# CANBed_FD.net
KiCad netlist of a schematic drawn in EAGLE
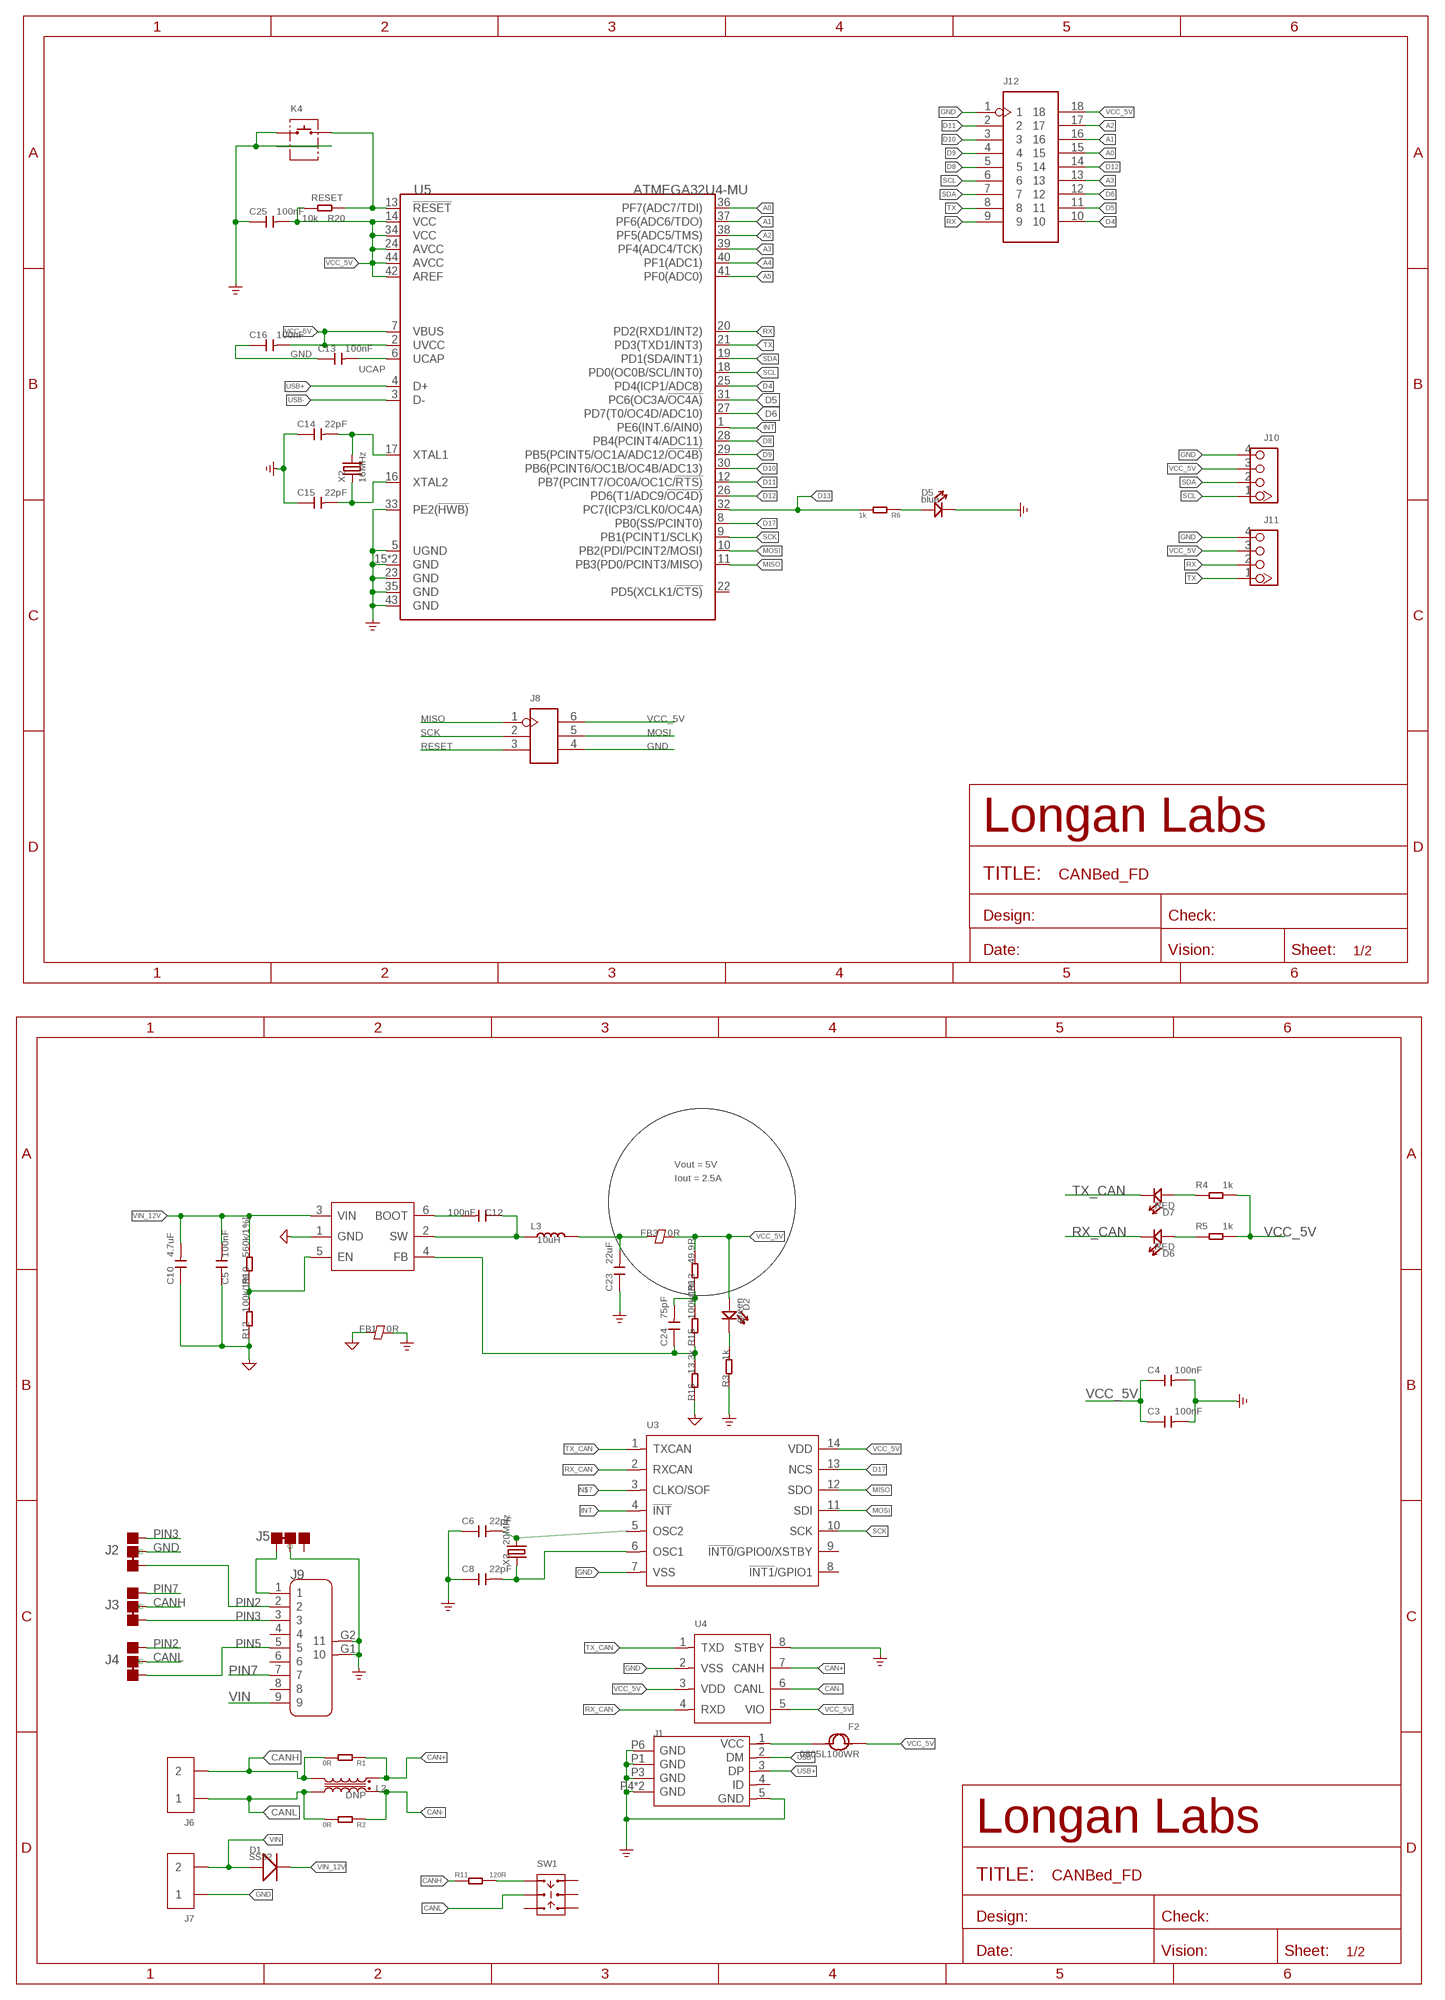
[diagram p0: schematic, sheet 1]

(export (version "E")
  (design (tool "Eeschema 10.0.6"))
  (components
    (comp (ref "C3")
      (value "100nF")
      (footprint "eagle-import:C0603")
      (libsource (lib "eagle-import") (part "CAP-0603"))
    )
    (comp (ref "C4")
      (value "100nF")
      (footprint "eagle-import:C0603")
      (libsource (lib "eagle-import") (part "CAP-0603"))
    )
    (comp (ref "C5")
      (value "100nF")
      (footprint "eagle-import:C0603")
      (libsource (lib "eagle-import") (part "CAP-0603"))
    )
    (comp (ref "C6")
      (value "22pF")
      (footprint "eagle-import:C0603")
      (libsource (lib "eagle-import") (part "CAP-0603"))
    )
    (comp (ref "C8")
      (value "22pF")
      (footprint "eagle-import:C0603")
      (libsource (lib "eagle-import") (part "CAP-0603"))
    )
    (comp (ref "C10")
      (value "4.7uF")
      (footprint "eagle-import:C1206")
      (libsource (lib "eagle-import") (part "CAP-1206"))
    )
    (comp (ref "C12")
      (value "100nF")
      (footprint "eagle-import:C0603")
      (libsource (lib "eagle-import") (part "CAP-0603"))
    )
    (comp (ref "C13")
      (value "100nF")
      (footprint "eagle-import:C0603")
      (libsource (lib "eagle-import") (part "CAP-0603"))
    )
    (comp (ref "C14")
      (value "22pF")
      (footprint "eagle-import:C0603")
      (libsource (lib "eagle-import") (part "CAP-0603"))
    )
    (comp (ref "C15")
      (value "22pF")
      (footprint "eagle-import:C0603")
      (libsource (lib "eagle-import") (part "CAP-0603"))
    )
    (comp (ref "C16")
      (value "100nF")
      (footprint "eagle-import:C0603")
      (libsource (lib "eagle-import") (part "CAP-0603"))
    )
    (comp (ref "C23")
      (value "22uF")
      (footprint "eagle-import:C1206")
      (libsource (lib "eagle-import") (part "CAP-1206"))
    )
    (comp (ref "C24")
      (value "75pF")
      (footprint "eagle-import:C0603")
      (libsource (lib "eagle-import") (part "CAP-0603"))
    )
    (comp (ref "C25")
      (value "100nF")
      (footprint "eagle-import:C0603")
      (libsource (lib "eagle-import") (part "CAP-0603"))
    )
    (comp (ref "D1")
      (value "SS32")
      (footprint "eagle-import:DO-214AC")
      (libsource (lib "eagle-import") (part "DIODE'SMA'"))
    )
    (comp (ref "D2")
      (value "green")
      (footprint "eagle-import:LED-0603")
      (libsource (lib "eagle-import") (part "LED'0603'"))
    )
    (comp (ref "D5")
      (value "blue")
      (footprint "eagle-import:LED-0603")
      (libsource (lib "eagle-import") (part "LED'0603'"))
    )
    (comp (ref "D6")
      (value "RED")
      (footprint "eagle-import:LED-0603")
      (libsource (lib "eagle-import") (part "LED'0603'"))
    )
    (comp (ref "D7")
      (value "RED")
      (footprint "eagle-import:LED-0603")
      (libsource (lib "eagle-import") (part "LED'0603'"))
    )
    (comp (ref "F2")
      (value "0805L100WR")
      (footprint "eagle-import:F0805")
      (libsource (lib "eagle-import") (part "FUSE0805"))
    )
    (comp (ref "FB1")
      (value "0R")
      (footprint "eagle-import:F0805")
      (libsource (lib "eagle-import") (part "FERRITE-BEAD-0805"))
    )
    (comp (ref "FB3")
      (value "0R")
      (footprint "eagle-import:F0805")
      (libsource (lib "eagle-import") (part "FERRITE-BEAD-0805"))
    )
    (comp (ref "J1")
      (value "MICRO-USB5+4P-320010050")
      (footprint "eagle-import:MICRO-USB5+5P-SMD-0.65-7.2X5.06MM")
      (libsource (lib "eagle-import") (part "MICRO-USB5+4P-320010050"))
    )
    (comp (ref "J2")
      (value "JUMPER-3P-SHORT")
      (footprint "eagle-import:3P-SMD-SHORT")
      (libsource (lib "eagle-import") (part "JUMPER-3P-SHORT"))
    )
    (comp (ref "J3")
      (value "JUMPER-3P-SHORT")
      (footprint "eagle-import:3P-SMD-SHORT")
      (libsource (lib "eagle-import") (part "JUMPER-3P-SHORT"))
    )
    (comp (ref "J4")
      (value "JUMPER-3P-SHORT")
      (footprint "eagle-import:3P-SMD-SHORT")
      (libsource (lib "eagle-import") (part "JUMPER-3P-SHORT"))
    )
    (comp (ref "J5")
      (value "JUMPER-3P-SHORT")
      (footprint "eagle-import:3P-SMD-SHORT")
      (libsource (lib "eagle-import") (part "JUMPER-3P-SHORT"))
    )
    (comp (ref "J6")
      (value "SCREW-TERMINAL-2P'5.08'")
      (footprint "eagle-import:H2-5.0-10.5X8.0MM")
      (libsource (lib "eagle-import") (part "SCREW-TERMINAL-2P'5.08'"))
    )
    (comp (ref "J7")
      (value "SCREW-TERMINAL-2P'5.08'")
      (footprint "eagle-import:H2-5.0-10.5X8.0MM")
      (libsource (lib "eagle-import") (part "SCREW-TERMINAL-2P'5.08'"))
    )
    (comp (ref "J8")
      (value "HEADER-2X3P-2.54")
      (footprint "eagle-import:H2X3-2.54")
      (libsource (lib "eagle-import") (part "HEADER-2X3P-2.54"))
    )
    (comp (ref "J9")
      (value "DB9'MEAL'")
      (footprint "eagle-import:DB9-MEAL")
      (libsource (lib "eagle-import") (part "DB9'MEAL'"))
    )
    (comp (ref "J10")
      (value "320110033")
      (footprint "eagle-import:HW4-2.0")
      (libsource (lib "eagle-import") (part "GROVE-CONNECTOR-DIP-2.0"))
    )
    (comp (ref "J11")
      (value "320110033")
      (footprint "eagle-import:HW4-2.0")
      (libsource (lib "eagle-import") (part "GROVE-CONNECTOR-DIP-2.0"))
    )
    (comp (ref "J12")
      (value "HEADER-2X9P-2.54")
      (footprint "eagle-import:H2X9-2.54")
      (libsource (lib "eagle-import") (part "HEADER-2X9P-2.54"))
    )
    (comp (ref "K4")
      (value "BUTTON-2+2P")
      (footprint "eagle-import:SW2+2P-7.7X2.75X3.95MM")
      (libsource (lib "eagle-import") (part "BUTTON-2+2P"))
    )
    (comp (ref "L2")
      (value "DNP")
      (footprint "eagle-import:INT4-0.85-2X1.25X1.2MM")
      (libsource (lib "eagle-import") (part "INDUCTOR-COMMON-MODE-SRF2012-900YA"))
    )
    (comp (ref "L3")
      (value "10uH")
      (footprint "eagle-import:INT2-SMD-6.6X7.1X3MM")
      (libsource (lib "eagle-import") (part "INDUCTOR-6.6X7.1"))
    )
    (comp (ref "R1")
      (value "0R")
      (footprint "eagle-import:R0603")
      (libsource (lib "eagle-import") (part "RES-0603"))
    )
    (comp (ref "R2")
      (value "0R")
      (footprint "eagle-import:R0603")
      (libsource (lib "eagle-import") (part "RES-0603"))
    )
    (comp (ref "R3")
      (value "1k")
      (footprint "eagle-import:R0603")
      (libsource (lib "eagle-import") (part "RES-0603"))
    )
    (comp (ref "R4")
      (value "1k")
      (footprint "eagle-import:R0603")
      (libsource (lib "eagle-import") (part "RES-0603"))
    )
    (comp (ref "R5")
      (value "1k")
      (footprint "eagle-import:R0603")
      (libsource (lib "eagle-import") (part "RES-0603"))
    )
    (comp (ref "R6")
      (value "1k")
      (footprint "eagle-import:R0603")
      (libsource (lib "eagle-import") (part "RES-0603"))
    )
    (comp (ref "R10")
      (value "560k/1%]")
      (footprint "eagle-import:R0603")
      (libsource (lib "eagle-import") (part "RES-0603"))
    )
    (comp (ref "R11")
      (value "120R")
      (footprint "eagle-import:R0603")
      (libsource (lib "eagle-import") (part "RES-0603"))
    )
    (comp (ref "R12")
      (value "100k/1%")
      (footprint "eagle-import:R0603")
      (libsource (lib "eagle-import") (part "RES-0603"))
    )
    (comp (ref "R13")
      (value "49.9R")
      (footprint "eagle-import:R0603")
      (libsource (lib "eagle-import") (part "RES-0603"))
    )
    (comp (ref "R15")
      (value "100k/1%")
      (footprint "eagle-import:R0603")
      (libsource (lib "eagle-import") (part "RES-0603"))
    )
    (comp (ref "R16")
      (value "13.3k")
      (footprint "eagle-import:R0603")
      (libsource (lib "eagle-import") (part "RES-0603"))
    )
    (comp (ref "R20")
      (value "10k")
      (footprint "eagle-import:R0603")
      (libsource (lib "eagle-import") (part "RES-0603"))
    )
    (comp (ref "SW1")
      (value "SWITCH-2CH-6P-311010004")
      (footprint "eagle-import:SW6-2.54-9.0X3.5X3.2+2.0MM")
      (libsource (lib "eagle-import") (part "SWITCH-2CH-6P-311010004"))
    )
    (comp (ref "U$11")
      (value "PMIC-TPS54302")
      (footprint "eagle-import:SOT-23-6")
      (libsource (lib "eagle-import") (part "PMIC-TPS54302"))
    )
    (comp (ref "U3")
      (value "CONTROLLER-MCP2517FD")
      (footprint "eagle-import:SOIC14-1.27-8.6X3.9MM")
      (libsource (lib "eagle-import") (part "CONTROLLER-MCP2517FD"))
    )
    (comp (ref "U4")
      (value "TRANSCEIVER-MCP2542")
      (footprint "eagle-import:SOIC8-1.27-5X4MM")
      (libsource (lib "eagle-import") (part "TRANSCEIVER-MCP2542"))
    )
    (comp (ref "U5")
      (value "ATMEGA32U4-MU")
      (footprint "eagle-import:QFN44")
      (libsource (lib "eagle-import") (part "ATMEGA32U4-MU"))
    )
    (comp (ref "X2")
      (value "16MHz")
      (footprint "eagle-import:HC49US")
      (libsource (lib "eagle-import") (part "CRYSTAL-2P'HC49US'"))
    )
    (comp (ref "X3")
      (value "20MHz")
      (footprint "eagle-import:HC49US")
      (libsource (lib "eagle-import") (part "CRYSTAL-2P'HC49US'"))
    )
  )
  (nets
    (net (code "1") (name "A0") (class "Default")
      (node (ref "J12") (pin "15") (pinfunction "15_15") (pintype "bidirectional"))
      (node (ref "U5") (pin "36") (pinfunction "PF7(ADC7/TDI)_36") (pintype "bidirectional"))
    )
    (net (code "2") (name "A1") (class "Default")
      (node (ref "J12") (pin "16") (pinfunction "16_16") (pintype "bidirectional"))
      (node (ref "U5") (pin "37") (pinfunction "PF6(ADC6/TDO)_37") (pintype "bidirectional"))
    )
    (net (code "3") (name "A2") (class "Default")
      (node (ref "J12") (pin "17") (pinfunction "17_17") (pintype "bidirectional"))
      (node (ref "U5") (pin "38") (pinfunction "PF5(ADC5/TMS)_38") (pintype "bidirectional"))
    )
    (net (code "4") (name "A3") (class "Default")
      (node (ref "J12") (pin "13") (pinfunction "13_13") (pintype "bidirectional"))
      (node (ref "U5") (pin "39") (pinfunction "PF4(ADC4/TCK)_39") (pintype "bidirectional"))
    )
    (net (code "5") (name "A4") (class "Default")
      (node (ref "U5") (pin "40") (pinfunction "PF1(ADC1)_40") (pintype "bidirectional"))
    )
    (net (code "6") (name "A5") (class "Default")
      (node (ref "U5") (pin "41") (pinfunction "PF0(ADC0)_41") (pintype "bidirectional"))
    )
    (net (code "7") (name "AGND") (class "Default")
      (node (ref "C10") (pin "1") (pinfunction "1_1") (pintype "passive"))
      (node (ref "C5") (pin "1") (pinfunction "1_1") (pintype "passive"))
      (node (ref "FB1") (pin "1") (pinfunction "1_1") (pintype "bidirectional"))
      (node (ref "R12") (pin "1") (pinfunction "1_1") (pintype "passive"))
      (node (ref "R16") (pin "1") (pinfunction "1_1") (pintype "passive"))
      (node (ref "U$11") (pin "1") (pinfunction "GND_1") (pintype "bidirectional"))
    )
    (net (code "8") (name "CAN+") (class "Default")
      (node (ref "L2") (pin "4") (pinfunction "4_4") (pintype "bidirectional"))
      (node (ref "R1") (pin "1") (pinfunction "1_1") (pintype "passive"))
      (node (ref "U4") (pin "7") (pinfunction "CANH_7") (pintype "bidirectional"))
    )
    (net (code "9") (name "CAN-") (class "Default")
      (node (ref "L2") (pin "1") (pinfunction "1_1") (pintype "bidirectional"))
      (node (ref "R2") (pin "1") (pinfunction "1_1") (pintype "passive"))
      (node (ref "U4") (pin "6") (pinfunction "CANL_6") (pintype "bidirectional"))
    )
    (net (code "10") (name "CANH") (class "Default")
      (node (ref "J3") (pin "MM") (pinfunction "C_MM") (pintype "bidirectional"))
      (node (ref "J6") (pin "2") (pinfunction "2_2") (pintype "bidirectional"))
      (node (ref "L2") (pin "3") (pinfunction "3_3") (pintype "bidirectional"))
      (node (ref "R1") (pin "2") (pinfunction "2_2") (pintype "passive"))
      (node (ref "R11") (pin "1") (pinfunction "1_1") (pintype "passive"))
    )
    (net (code "11") (name "CANL") (class "Default")
      (node (ref "J4") (pin "MM") (pinfunction "C_MM") (pintype "bidirectional"))
      (node (ref "J6") (pin "1") (pinfunction "1_1") (pintype "bidirectional"))
      (node (ref "L2") (pin "2") (pinfunction "2_2") (pintype "bidirectional"))
      (node (ref "R2") (pin "2") (pinfunction "2_2") (pintype "passive"))
      (node (ref "SW1") (pin "COM1") (pinfunction "COM1_COM1") (pintype "bidirectional"))
    )
    (net (code "12") (name "D4") (class "Default")
      (node (ref "J12") (pin "10") (pinfunction "10_10") (pintype "bidirectional"))
      (node (ref "U5") (pin "25") (pinfunction "PD4(ICP1/ADC8)_25") (pintype "bidirectional"))
    )
    (net (code "13") (name "D5") (class "Default")
      (node (ref "J12") (pin "11") (pinfunction "11_11") (pintype "bidirectional"))
      (node (ref "U5") (pin "31") (pinfunction "PC6(OC3A/~{OC4A})_31") (pintype "bidirectional"))
    )
    (net (code "14") (name "D6") (class "Default")
      (node (ref "J12") (pin "12") (pinfunction "12_12") (pintype "bidirectional"))
      (node (ref "U5") (pin "27") (pinfunction "PD7(T0/OC4D/ADC10)_27") (pintype "bidirectional"))
    )
    (net (code "15") (name "D8") (class "Default")
      (node (ref "J12") (pin "5") (pinfunction "5_5") (pintype "bidirectional"))
      (node (ref "U5") (pin "28") (pinfunction "PB4(PCINT4/ADC11)_28") (pintype "bidirectional"))
    )
    (net (code "16") (name "D9") (class "Default")
      (node (ref "J12") (pin "4") (pinfunction "4_4") (pintype "bidirectional"))
      (node (ref "U5") (pin "29") (pinfunction "PB5(PCINT5/OC1A/ADC12/~{OC4B})_29") (pintype "bidirectional"))
    )
    (net (code "17") (name "D10") (class "Default")
      (node (ref "J12") (pin "3") (pinfunction "3_3") (pintype "bidirectional"))
      (node (ref "U5") (pin "30") (pinfunction "PB6(PCINT6/OC1B/OC4B/ADC13)_30") (pintype "bidirectional"))
    )
    (net (code "18") (name "D11") (class "Default")
      (node (ref "J12") (pin "2") (pinfunction "2_2") (pintype "bidirectional"))
      (node (ref "U5") (pin "12") (pinfunction "PB7(PCINT7/OC0A/OC1C/~{RTS})_12") (pintype "bidirectional"))
    )
    (net (code "19") (name "D12") (class "Default")
      (node (ref "J12") (pin "14") (pinfunction "14_14") (pintype "bidirectional"))
      (node (ref "U5") (pin "26") (pinfunction "PD6(T1/ADC9/~{OC4D})_26") (pintype "bidirectional"))
    )
    (net (code "20") (name "D13") (class "Default")
      (node (ref "R6") (pin "2") (pinfunction "2_2") (pintype "passive"))
      (node (ref "U5") (pin "32") (pinfunction "PC7(ICP3/CLK0/OC4A)_32") (pintype "bidirectional"))
    )
    (net (code "21") (name "D17") (class "Default")
      (node (ref "U3") (pin "13") (pinfunction "NCS_13") (pintype "bidirectional"))
      (node (ref "U5") (pin "8") (pinfunction "PB0(SS/PCINT0)_8") (pintype "bidirectional"))
    )
    (net (code "22") (name "GND") (class "Default")
      (node (ref "C13") (pin "1") (pinfunction "1_1") (pintype "passive"))
      (node (ref "C14") (pin "1") (pinfunction "1_1") (pintype "passive"))
      (node (ref "C15") (pin "1") (pinfunction "1_1") (pintype "passive"))
      (node (ref "C16") (pin "1") (pinfunction "1_1") (pintype "passive"))
      (node (ref "C23") (pin "1") (pinfunction "1_1") (pintype "passive"))
      (node (ref "C25") (pin "1") (pinfunction "1_1") (pintype "passive"))
      (node (ref "C3") (pin "2") (pinfunction "2_2") (pintype "passive"))
      (node (ref "C4") (pin "2") (pinfunction "2_2") (pintype "passive"))
      (node (ref "C6") (pin "1") (pinfunction "1_1") (pintype "passive"))
      (node (ref "C8") (pin "1") (pinfunction "1_1") (pintype "passive"))
      (node (ref "D5") (pin "-") (pinfunction "-_-") (pintype "passive"))
      (node (ref "FB1") (pin "2") (pinfunction "2_2") (pintype "bidirectional"))
      (node (ref "J1") (pin "5") (pinfunction "GND_5") (pintype "bidirectional"))
      (node (ref "J1") (pin "P1") (pinfunction "GND_P1") (pintype "bidirectional"))
      (node (ref "J1") (pin "P3") (pinfunction "GND_P3") (pintype "bidirectional"))
      (node (ref "J1") (pin "P4") (pinfunction "GND_P4") (pintype "bidirectional"))
      (node (ref "J1") (pin "P5") (pinfunction "GND_P5") (pintype "bidirectional"))
      (node (ref "J1") (pin "P6") (pinfunction "GND_P6") (pintype "bidirectional"))
      (node (ref "J10") (pin "4") (pinfunction "4_4") (pintype "bidirectional"))
      (node (ref "J11") (pin "4") (pinfunction "4_4") (pintype "bidirectional"))
      (node (ref "J12") (pin "1") (pinfunction "1_1") (pintype "bidirectional"))
      (node (ref "J2") (pin "MM") (pinfunction "C_MM") (pintype "bidirectional"))
      (node (ref "J5") (pin "MM") (pinfunction "C_MM") (pintype "bidirectional"))
      (node (ref "J7") (pin "1") (pinfunction "1_1") (pintype "bidirectional"))
      (node (ref "J8") (pin "4") (pinfunction "4_4") (pintype "bidirectional"))
      (node (ref "J9") (pin "G1") (pinfunction "10_G1") (pintype "bidirectional"))
      (node (ref "J9") (pin "G2") (pinfunction "11_G2") (pintype "bidirectional"))
      (node (ref "K4") (pin "1") (pinfunction "1_1") (pintype "bidirectional"))
      (node (ref "K4") (pin "S1") (pinfunction "S1_S1") (pintype "bidirectional"))
      (node (ref "K4") (pin "S2") (pinfunction "S2_S2") (pintype "bidirectional"))
      (node (ref "R3") (pin "1") (pinfunction "1_1") (pintype "passive"))
      (node (ref "U3") (pin "7") (pinfunction "VSS_7") (pintype "bidirectional"))
      (node (ref "U4") (pin "2") (pinfunction "VSS_2") (pintype "bidirectional"))
      (node (ref "U4") (pin "8") (pinfunction "STBY_8") (pintype "bidirectional"))
      (node (ref "U5") (pin "15") (pinfunction "GND_15") (pintype "bidirectional"))
      (node (ref "U5") (pin "23") (pinfunction "GND_23") (pintype "bidirectional"))
      (node (ref "U5") (pin "33") (pinfunction "PE2(~{HWB})_33") (pintype "bidirectional"))
      (node (ref "U5") (pin "35") (pinfunction "GND_35") (pintype "bidirectional"))
      (node (ref "U5") (pin "43") (pinfunction "GND_43") (pintype "bidirectional"))
      (node (ref "U5") (pin "5") (pinfunction "UGND_5") (pintype "bidirectional"))
      (node (ref "U5") (pin "TAB") (pinfunction "GND_TAB") (pintype "bidirectional"))
    )
    (net (code "23") (name "INT") (class "Default")
      (node (ref "U3") (pin "4") (pinfunction "~{INT}_4") (pintype "bidirectional"))
      (node (ref "U5") (pin "1") (pinfunction "PE6(INT.6/AIN0)_1") (pintype "bidirectional"))
    )
    (net (code "24") (name "MISO") (class "Default")
      (node (ref "J8") (pin "1") (pinfunction "1_1") (pintype "bidirectional"))
      (node (ref "U3") (pin "12") (pinfunction "SDO_12") (pintype "bidirectional"))
      (node (ref "U5") (pin "11") (pinfunction "PB3(PD0/PCINT3/MISO)_11") (pintype "bidirectional"))
    )
    (net (code "25") (name "MOSI") (class "Default")
      (node (ref "J8") (pin "5") (pinfunction "5_5") (pintype "bidirectional"))
      (node (ref "U3") (pin "11") (pinfunction "SDI_11") (pintype "bidirectional"))
      (node (ref "U5") (pin "10") (pinfunction "PB2(PDI/PCINT2/MOSI)_10") (pintype "bidirectional"))
    )
    (net (code "26") (name "N$7") (class "Default")
      (node (ref "U3") (pin "3") (pinfunction "CLKO/SOF_3") (pintype "bidirectional"))
    )
    (net (code "27") (name "Net-(C23-Pad2)") (class "Default")
      (node (ref "C23") (pin "2") (pinfunction "2_2") (pintype "passive"))
      (node (ref "FB3") (pin "1") (pinfunction "1_1") (pintype "bidirectional"))
      (node (ref "L3") (pin "2") (pinfunction "2_2") (pintype "passive"))
    )
    (net (code "28") (name "Net-(C24-Pad2)") (class "Default")
      (node (ref "C24") (pin "2") (pinfunction "2_2") (pintype "passive"))
      (node (ref "R13") (pin "1") (pinfunction "1_1") (pintype "passive"))
      (node (ref "R15") (pin "2") (pinfunction "2_2") (pintype "passive"))
    )
    (net (code "29") (name "Net-(D2-Pad-)") (class "Default")
      (node (ref "D2") (pin "-") (pinfunction "-_-") (pintype "passive"))
      (node (ref "R3") (pin "2") (pinfunction "2_2") (pintype "passive"))
    )
    (net (code "30") (name "Net-(D5-Pad+)") (class "Default")
      (node (ref "D5") (pin "+") (pinfunction "+_+") (pintype "passive"))
      (node (ref "R6") (pin "1") (pinfunction "1_1") (pintype "passive"))
    )
    (net (code "31") (name "Net-(D6-Pad+)") (class "Default")
      (node (ref "D6") (pin "+") (pinfunction "+_+") (pintype "passive"))
      (node (ref "R5") (pin "1") (pinfunction "1_1") (pintype "passive"))
    )
    (net (code "32") (name "Net-(D7-Pad+)") (class "Default")
      (node (ref "D7") (pin "+") (pinfunction "+_+") (pintype "passive"))
      (node (ref "R4") (pin "1") (pinfunction "1_1") (pintype "passive"))
    )
    (net (code "33") (name "Net-(J1-VCC)") (class "Default")
      (node (ref "F2") (pin "2") (pinfunction "2_2") (pintype "bidirectional"))
      (node (ref "J1") (pin "1") (pinfunction "VCC_1") (pintype "bidirectional"))
    )
    (net (code "34") (name "Net-(J5-L)") (class "Default")
      (node (ref "J5") (pin "11") (pinfunction "L_11") (pintype "bidirectional"))
      (node (ref "J9") (pin "1") (pinfunction "1_1") (pintype "bidirectional"))
    )
    (net (code "35") (name "Net-(R11-Pad2)") (class "Default")
      (node (ref "R11") (pin "2") (pinfunction "2_2") (pintype "passive"))
      (node (ref "SW1") (pin "CH1A") (pinfunction "CH1A_CH1A") (pintype "bidirectional"))
    )
    (net (code "36") (name "Net-(U$11-BOOT)") (class "Default")
      (node (ref "C12") (pin "2") (pinfunction "2_2") (pintype "passive"))
      (node (ref "U$11") (pin "6") (pinfunction "BOOT_6") (pintype "bidirectional"))
    )
    (net (code "37") (name "Net-(U$11-EN)") (class "Default")
      (node (ref "R10") (pin "1") (pinfunction "1_1") (pintype "passive"))
      (node (ref "R12") (pin "2") (pinfunction "2_2") (pintype "passive"))
      (node (ref "U$11") (pin "5") (pinfunction "EN_5") (pintype "bidirectional"))
    )
    (net (code "38") (name "Net-(U$11-FB)") (class "Default")
      (node (ref "C24") (pin "1") (pinfunction "1_1") (pintype "passive"))
      (node (ref "R15") (pin "1") (pinfunction "1_1") (pintype "passive"))
      (node (ref "R16") (pin "2") (pinfunction "2_2") (pintype "passive"))
      (node (ref "U$11") (pin "4") (pinfunction "FB_4") (pintype "bidirectional"))
    )
    (net (code "39") (name "Net-(U$11-SW)") (class "Default")
      (node (ref "C12") (pin "1") (pinfunction "1_1") (pintype "passive"))
      (node (ref "L3") (pin "1") (pinfunction "1_1") (pintype "passive"))
      (node (ref "U$11") (pin "2") (pinfunction "SW_2") (pintype "bidirectional"))
    )
    (net (code "40") (name "Net-(U3-OSC1)") (class "Default")
      (node (ref "C8") (pin "2") (pinfunction "2_2") (pintype "passive"))
      (node (ref "U3") (pin "6") (pinfunction "OSC1_6") (pintype "bidirectional"))
      (node (ref "X3") (pin "1") (pinfunction "1_1") (pintype "passive"))
    )
    (net (code "41") (name "Net-(U3-OSC2)") (class "Default")
      (node (ref "C6") (pin "2") (pinfunction "2_2") (pintype "passive"))
      (node (ref "U3") (pin "5") (pinfunction "OSC2_5") (pintype "bidirectional"))
      (node (ref "X3") (pin "2") (pinfunction "2_2") (pintype "passive"))
    )
    (net (code "42") (name "Net-(U5-XTAL1)") (class "Default")
      (node (ref "C14") (pin "2") (pinfunction "2_2") (pintype "passive"))
      (node (ref "U5") (pin "17") (pinfunction "XTAL1_17") (pintype "bidirectional"))
      (node (ref "X2") (pin "2") (pinfunction "2_2") (pintype "passive"))
    )
    (net (code "43") (name "Net-(U5-XTAL2)") (class "Default")
      (node (ref "C15") (pin "2") (pinfunction "2_2") (pintype "passive"))
      (node (ref "U5") (pin "16") (pinfunction "XTAL2_16") (pintype "bidirectional"))
      (node (ref "X2") (pin "1") (pinfunction "1_1") (pintype "passive"))
    )
    (net (code "44") (name "PIN2") (class "Default")
      (node (ref "J2") (pin "11") (pinfunction "L_11") (pintype "bidirectional"))
      (node (ref "J4") (pin "00") (pinfunction "R_00") (pintype "bidirectional"))
      (node (ref "J9") (pin "2") (pinfunction "2_2") (pintype "bidirectional"))
    )
    (net (code "45") (name "PIN3") (class "Default")
      (node (ref "J2") (pin "00") (pinfunction "R_00") (pintype "bidirectional"))
      (node (ref "J3") (pin "11") (pinfunction "L_11") (pintype "bidirectional"))
      (node (ref "J9") (pin "3") (pinfunction "3_3") (pintype "bidirectional"))
    )
    (net (code "46") (name "PIN5") (class "Default")
      (node (ref "J4") (pin "11") (pinfunction "L_11") (pintype "bidirectional"))
      (node (ref "J9") (pin "5") (pinfunction "5_5") (pintype "bidirectional"))
    )
    (net (code "47") (name "PIN7") (class "Default")
      (node (ref "J3") (pin "00") (pinfunction "R_00") (pintype "bidirectional"))
      (node (ref "J9") (pin "7") (pinfunction "7_7") (pintype "bidirectional"))
    )
    (net (code "48") (name "RESET") (class "Default")
      (node (ref "J8") (pin "3") (pinfunction "3_3") (pintype "bidirectional"))
      (node (ref "K4") (pin "2") (pinfunction "2_2") (pintype "bidirectional"))
      (node (ref "R20") (pin "1") (pinfunction "1_1") (pintype "passive"))
      (node (ref "U5") (pin "13") (pinfunction "~{RESET}_13") (pintype "bidirectional"))
    )
    (net (code "49") (name "RX") (class "Default")
      (node (ref "J11") (pin "2") (pinfunction "2_2") (pintype "bidirectional"))
      (node (ref "J12") (pin "9") (pinfunction "9_9") (pintype "bidirectional"))
      (node (ref "U5") (pin "20") (pinfunction "PD2(RXD1/INT2)_20") (pintype "bidirectional"))
    )
    (net (code "50") (name "RX_CAN") (class "Default")
      (node (ref "D6") (pin "-") (pinfunction "-_-") (pintype "passive"))
      (node (ref "U3") (pin "2") (pinfunction "RXCAN_2") (pintype "bidirectional"))
      (node (ref "U4") (pin "4") (pinfunction "RXD_4") (pintype "bidirectional"))
    )
    (net (code "51") (name "SCK") (class "Default")
      (node (ref "J8") (pin "2") (pinfunction "2_2") (pintype "bidirectional"))
      (node (ref "U3") (pin "10") (pinfunction "SCK_10") (pintype "bidirectional"))
      (node (ref "U5") (pin "9") (pinfunction "PB1(PCINT1/SCLK)_9") (pintype "bidirectional"))
    )
    (net (code "52") (name "SCL") (class "Default")
      (node (ref "J10") (pin "1") (pinfunction "1_1") (pintype "bidirectional"))
      (node (ref "J12") (pin "6") (pinfunction "6_6") (pintype "bidirectional"))
      (node (ref "U5") (pin "18") (pinfunction "PD0(OC0B/SCL/INT0)_18") (pintype "bidirectional"))
    )
    (net (code "53") (name "SDA") (class "Default")
      (node (ref "J10") (pin "2") (pinfunction "2_2") (pintype "bidirectional"))
      (node (ref "J12") (pin "7") (pinfunction "7_7") (pintype "bidirectional"))
      (node (ref "U5") (pin "19") (pinfunction "PD1(SDA/INT1)_19") (pintype "bidirectional"))
    )
    (net (code "54") (name "TX") (class "Default")
      (node (ref "J11") (pin "1") (pinfunction "1_1") (pintype "bidirectional"))
      (node (ref "J12") (pin "8") (pinfunction "8_8") (pintype "bidirectional"))
      (node (ref "U5") (pin "21") (pinfunction "PD3(TXD1/INT3)_21") (pintype "bidirectional"))
    )
    (net (code "55") (name "TX_CAN") (class "Default")
      (node (ref "D7") (pin "-") (pinfunction "-_-") (pintype "passive"))
      (node (ref "U3") (pin "1") (pinfunction "TXCAN_1") (pintype "bidirectional"))
      (node (ref "U4") (pin "1") (pinfunction "TXD_1") (pintype "bidirectional"))
    )
    (net (code "56") (name "UCAP") (class "Default")
      (node (ref "C13") (pin "2") (pinfunction "2_2") (pintype "passive"))
      (node (ref "U5") (pin "6") (pinfunction "UCAP_6") (pintype "bidirectional"))
    )
    (net (code "57") (name "USB+") (class "Default")
      (node (ref "J1") (pin "3") (pinfunction "DP_3") (pintype "bidirectional"))
      (node (ref "U5") (pin "4") (pinfunction "D+_4") (pintype "bidirectional"))
    )
    (net (code "58") (name "USB-") (class "Default")
      (node (ref "J1") (pin "2") (pinfunction "DM_2") (pintype "bidirectional"))
      (node (ref "U5") (pin "3") (pinfunction "D-_3") (pintype "bidirectional"))
    )
    (net (code "59") (name "VCC_5V") (class "Default")
      (node (ref "C16") (pin "2") (pinfunction "2_2") (pintype "passive"))
      (node (ref "C25") (pin "2") (pinfunction "2_2") (pintype "passive"))
      (node (ref "C3") (pin "1") (pinfunction "1_1") (pintype "passive"))
      (node (ref "C4") (pin "1") (pinfunction "1_1") (pintype "passive"))
      (node (ref "D2") (pin "+") (pinfunction "+_+") (pintype "passive"))
      (node (ref "F2") (pin "1") (pinfunction "1_1") (pintype "bidirectional"))
      (node (ref "FB3") (pin "2") (pinfunction "2_2") (pintype "bidirectional"))
      (node (ref "J10") (pin "3") (pinfunction "3_3") (pintype "bidirectional"))
      (node (ref "J11") (pin "3") (pinfunction "3_3") (pintype "bidirectional"))
      (node (ref "J12") (pin "18") (pinfunction "18_18") (pintype "bidirectional"))
      (node (ref "J8") (pin "6") (pinfunction "6_6") (pintype "bidirectional"))
      (node (ref "R13") (pin "2") (pinfunction "2_2") (pintype "passive"))
      (node (ref "R20") (pin "2") (pinfunction "2_2") (pintype "passive"))
      (node (ref "R4") (pin "2") (pinfunction "2_2") (pintype "passive"))
      (node (ref "R5") (pin "2") (pinfunction "2_2") (pintype "passive"))
      (node (ref "U3") (pin "14") (pinfunction "VDD_14") (pintype "bidirectional"))
      (node (ref "U4") (pin "3") (pinfunction "VDD_3") (pintype "bidirectional"))
      (node (ref "U4") (pin "5") (pinfunction "VIO_5") (pintype "bidirectional"))
      (node (ref "U5") (pin "14") (pinfunction "VCC_14") (pintype "bidirectional"))
      (node (ref "U5") (pin "2") (pinfunction "UVCC_2") (pintype "bidirectional"))
      (node (ref "U5") (pin "24") (pinfunction "AVCC_24") (pintype "bidirectional"))
      (node (ref "U5") (pin "34") (pinfunction "VCC_34") (pintype "bidirectional"))
      (node (ref "U5") (pin "42") (pinfunction "AREF_42") (pintype "bidirectional"))
      (node (ref "U5") (pin "44") (pinfunction "AVCC_44") (pintype "bidirectional"))
      (node (ref "U5") (pin "7") (pinfunction "VBUS_7") (pintype "bidirectional"))
    )
    (net (code "60") (name "VIN") (class "Default")
      (node (ref "D1") (pin "1") (pinfunction "+_1") (pintype "passive"))
      (node (ref "J7") (pin "2") (pinfunction "2_2") (pintype "bidirectional"))
      (node (ref "J9") (pin "9") (pinfunction "9_9") (pintype "bidirectional"))
    )
    (net (code "61") (name "VIN_12V") (class "Default")
      (node (ref "C10") (pin "2") (pinfunction "2_2") (pintype "passive"))
      (node (ref "C5") (pin "2") (pinfunction "2_2") (pintype "passive"))
      (node (ref "D1") (pin "2") (pinfunction "-_2") (pintype "passive"))
      (node (ref "R10") (pin "2") (pinfunction "2_2") (pintype "passive"))
      (node (ref "U$11") (pin "3") (pinfunction "VIN_3") (pintype "bidirectional"))
    )
    (net (code "62") (name "unconnected-(J1-ID-Pad4)") (class "Default")
      (node (ref "J1") (pin "4") (pinfunction "ID_4") (pintype "bidirectional"))
    )
    (net (code "63") (name "unconnected-(J5-R-Pad00)") (class "Default")
      (node (ref "J5") (pin "00") (pinfunction "R_00") (pintype "bidirectional"))
    )
    (net (code "64") (name "unconnected-(J9-Pad4)") (class "Default")
      (node (ref "J9") (pin "4") (pinfunction "4_4") (pintype "bidirectional"))
    )
    (net (code "65") (name "unconnected-(J9-Pad6)") (class "Default")
      (node (ref "J9") (pin "6") (pinfunction "6_6") (pintype "bidirectional"))
    )
    (net (code "66") (name "unconnected-(J9-Pad8)") (class "Default")
      (node (ref "J9") (pin "8") (pinfunction "8_8") (pintype "bidirectional"))
    )
    (net (code "67") (name "unconnected-(SW1-PadCH1B)") (class "Default")
      (node (ref "SW1") (pin "CH1B") (pinfunction "CH1B_CH1B") (pintype "bidirectional"))
    )
    (net (code "68") (name "unconnected-(SW1-PadCH2A)") (class "Default")
      (node (ref "SW1") (pin "CH2A") (pinfunction "CH2A_CH2A") (pintype "bidirectional"))
    )
    (net (code "69") (name "unconnected-(SW1-PadCH2B)") (class "Default")
      (node (ref "SW1") (pin "CH2B") (pinfunction "CH2B_CH2B") (pintype "bidirectional"))
    )
    (net (code "70") (name "unconnected-(SW1-PadCOM2)") (class "Default")
      (node (ref "SW1") (pin "COM2") (pinfunction "COM2_COM2") (pintype "bidirectional"))
    )
    (net (code "71") (name "unconnected-(U3-~{INT0}{slash}GPIO0{slash}XSTBY-Pad9)") (class "Default")
      (node (ref "U3") (pin "9") (pinfunction "~{INT0}/GPIO0/XSTBY_9") (pintype "bidirectional"))
    )
    (net (code "72") (name "unconnected-(U3-~{INT1}{slash}GPIO1-Pad8)") (class "Default")
      (node (ref "U3") (pin "8") (pinfunction "~{INT1}/GPIO1_8") (pintype "bidirectional"))
    )
    (net (code "73") (name "unconnected-(U5-PD5(XCLK1{slash}~{CTS})-Pad22)") (class "Default")
      (node (ref "U5") (pin "22") (pinfunction "PD5(XCLK1/~{CTS})_22") (pintype "bidirectional"))
    )
  )
)
